# detector03.net
KiCad netlist of a schematic drawn in EAGLE
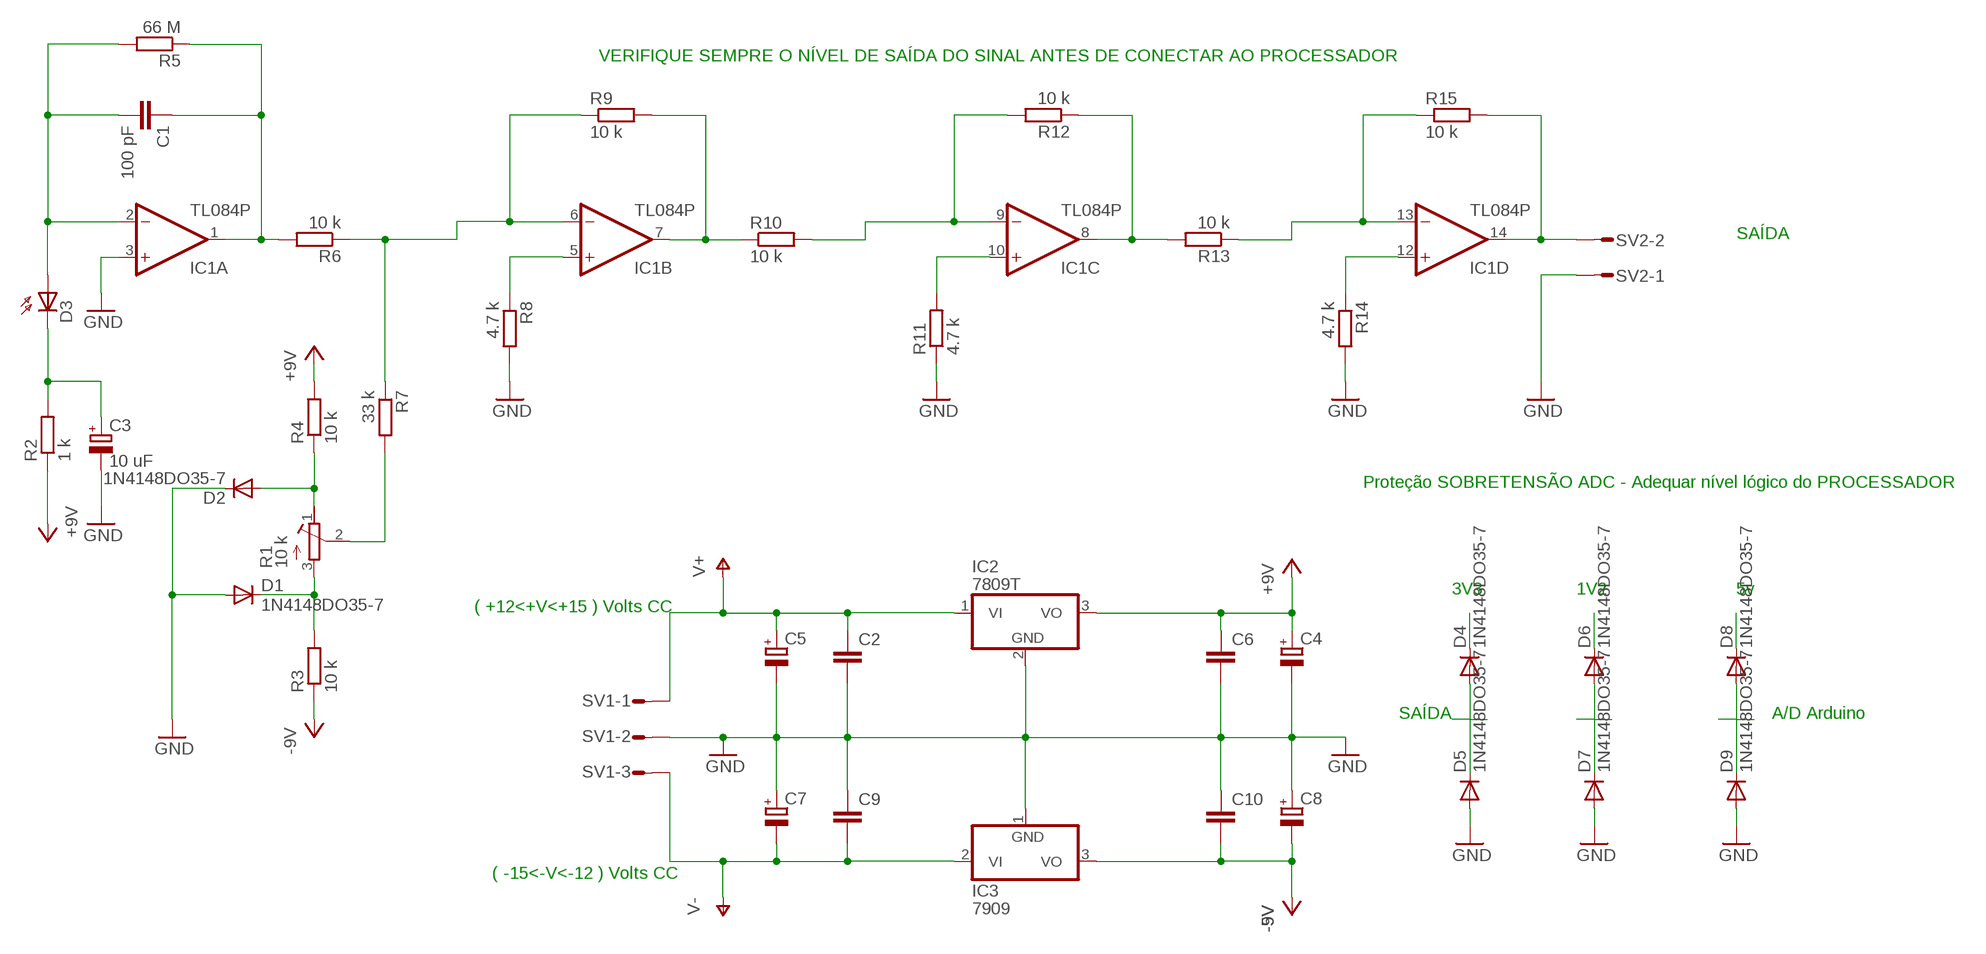
[diagram p0: schematic, sheet 1]

(export (version "E")
  (design (tool "Eeschema 10.0.6"))
  (components
    (comp (ref "C1")
      (value "100 pF")
      (footprint "eagle-import:C050-045X075")
      (libsource (lib "eagle-import") (part "C-EU050-045X075"))
    )
    (comp (ref "C2")
      (value "C-EU050-045X075")
      (footprint "eagle-import:C050-045X075")
      (libsource (lib "eagle-import") (part "C-EU050-045X075"))
    )
    (comp (ref "C3")
      (value "10 uF")
      (footprint "eagle-import:E3,5-8")
      (libsource (lib "eagle-import") (part "CPOL-EUE3.5-8"))
    )
    (comp (ref "C4")
      (value "CPOL-EUE3.5-8")
      (footprint "eagle-import:E3,5-8")
      (libsource (lib "eagle-import") (part "CPOL-EUE3.5-8"))
    )
    (comp (ref "C5")
      (value "CPOL-EUE3.5-8")
      (footprint "eagle-import:E3,5-8")
      (libsource (lib "eagle-import") (part "CPOL-EUE3.5-8"))
    )
    (comp (ref "C6")
      (value "C-EU050-045X075")
      (footprint "eagle-import:C050-045X075")
      (libsource (lib "eagle-import") (part "C-EU050-045X075"))
    )
    (comp (ref "C7")
      (value "CPOL-EUE3.5-8")
      (footprint "eagle-import:E3,5-8")
      (libsource (lib "eagle-import") (part "CPOL-EUE3.5-8"))
    )
    (comp (ref "C8")
      (value "CPOL-EUE3.5-8")
      (footprint "eagle-import:E3,5-8")
      (libsource (lib "eagle-import") (part "CPOL-EUE3.5-8"))
    )
    (comp (ref "C9")
      (value "C-EU050-045X075")
      (footprint "eagle-import:C050-045X075")
      (libsource (lib "eagle-import") (part "C-EU050-045X075"))
    )
    (comp (ref "C10")
      (value "C-EU050-045X075")
      (footprint "eagle-import:C050-045X075")
      (libsource (lib "eagle-import") (part "C-EU050-045X075"))
    )
    (comp (ref "D1")
      (value "1N4148DO35-7")
      (footprint "eagle-import:DO35-7")
      (libsource (lib "eagle-import") (part "1N4148DO35-7"))
    )
    (comp (ref "D2")
      (value "1N4148DO35-7")
      (footprint "eagle-import:DO35-7")
      (libsource (lib "eagle-import") (part "1N4148DO35-7"))
    )
    (comp (ref "D3")
      (value "SFH225")
      (footprint "eagle-import:SFH225")
      (libsource (lib "eagle-import") (part "SFH225"))
    )
    (comp (ref "D4")
      (value "1N4148DO35-7")
      (footprint "eagle-import:DO35-7")
      (libsource (lib "eagle-import") (part "1N4148DO35-7"))
    )
    (comp (ref "D5")
      (value "1N4148DO35-7")
      (footprint "eagle-import:DO35-7")
      (libsource (lib "eagle-import") (part "1N4148DO35-7"))
    )
    (comp (ref "D6")
      (value "1N4148DO35-7")
      (footprint "eagle-import:DO35-7")
      (libsource (lib "eagle-import") (part "1N4148DO35-7"))
    )
    (comp (ref "D7")
      (value "1N4148DO35-7")
      (footprint "eagle-import:DO35-7")
      (libsource (lib "eagle-import") (part "1N4148DO35-7"))
    )
    (comp (ref "D8")
      (value "1N4148DO35-7")
      (footprint "eagle-import:DO35-7")
      (libsource (lib "eagle-import") (part "1N4148DO35-7"))
    )
    (comp (ref "D9")
      (value "1N4148DO35-7")
      (footprint "eagle-import:DO35-7")
      (libsource (lib "eagle-import") (part "1N4148DO35-7"))
    )
    (comp (ref "IC1")
      (value "TL084P")
      (footprint "eagle-import:DIL14")
      (libsource (lib "eagle-import") (part "TL084P"))
    )
    (comp (ref "IC2")
      (value "7809T")
      (footprint "eagle-import:TO220H")
      (libsource (lib "eagle-import") (part "78T05"))
    )
    (comp (ref "IC3")
      (value "7909")
      (footprint "eagle-import:TO220H")
      (libsource (lib "eagle-import") (part "79T08"))
    )
    (comp (ref "R1")
      (value "10 k")
      (footprint "eagle-import:RTRIMT93YA")
      (libsource (lib "eagle-import") (part "R-TRIMMT93YA"))
    )
    (comp (ref "R2")
      (value "1 k")
      (footprint "eagle-import:0207_7")
      (libsource (lib "eagle-import") (part "R-EU_0207/7"))
    )
    (comp (ref "R3")
      (value "10 k")
      (footprint "eagle-import:0207_7")
      (libsource (lib "eagle-import") (part "R-EU_0207/7"))
    )
    (comp (ref "R4")
      (value "10 k")
      (footprint "eagle-import:0207_7")
      (libsource (lib "eagle-import") (part "R-EU_0207/7"))
    )
    (comp (ref "R5")
      (value "66 M")
      (footprint "eagle-import:0207_7")
      (libsource (lib "eagle-import") (part "R-EU_0207/7"))
    )
    (comp (ref "R6")
      (value "10 k")
      (footprint "eagle-import:0207_7")
      (libsource (lib "eagle-import") (part "R-EU_0207/7"))
    )
    (comp (ref "R7")
      (value "33 k")
      (footprint "eagle-import:0207_7")
      (libsource (lib "eagle-import") (part "R-EU_0207/7"))
    )
    (comp (ref "R8")
      (value "4.7 k")
      (footprint "eagle-import:0207_7")
      (libsource (lib "eagle-import") (part "R-EU_0207/7"))
    )
    (comp (ref "R9")
      (value "10 k")
      (footprint "eagle-import:0207_7")
      (libsource (lib "eagle-import") (part "R-EU_0207/7"))
    )
    (comp (ref "R10")
      (value "10 k")
      (footprint "eagle-import:0207_7")
      (libsource (lib "eagle-import") (part "R-EU_0207/7"))
    )
    (comp (ref "R11")
      (value "4.7 k")
      (footprint "eagle-import:0207_7")
      (libsource (lib "eagle-import") (part "R-EU_0207/7"))
    )
    (comp (ref "R12")
      (value "10 k")
      (footprint "eagle-import:0207_7")
      (libsource (lib "eagle-import") (part "R-EU_0207/7"))
    )
    (comp (ref "R13")
      (value "10 k")
      (footprint "eagle-import:0207_7")
      (libsource (lib "eagle-import") (part "R-EU_0207/7"))
    )
    (comp (ref "R14")
      (value "4.7 k")
      (footprint "eagle-import:0207_7")
      (libsource (lib "eagle-import") (part "R-EU_0207/7"))
    )
    (comp (ref "R15")
      (value "10 k")
      (footprint "eagle-import:0207_7")
      (libsource (lib "eagle-import") (part "R-EU_0207/7"))
    )
    (comp (ref "SV1")
      (value "L03P")
      (footprint "eagle-import:L03P")
      (libsource (lib "eagle-import") (part "L03P"))
    )
    (comp (ref "SV2")
      (value "L02P")
      (footprint "eagle-import:L02P")
      (libsource (lib "eagle-import") (part "L02P"))
    )
  )
  (nets
    (net (code "1") (name "+9V") (class "Default")
      (node (ref "C4") (pin "+") (pinfunction "+_+") (pintype "passive"))
      (node (ref "C6") (pin "1") (pinfunction "1_1") (pintype "passive"))
      (node (ref "IC2") (pin "3") (pinfunction "VO_3") (pintype "passive"))
      (node (ref "R2") (pin "1") (pinfunction "1_1") (pintype "passive"))
      (node (ref "R4") (pin "2") (pinfunction "2_2") (pintype "passive"))
    )
    (net (code "2") (name "-5V") (class "Default")
      (node (ref "C10") (pin "2") (pinfunction "2_2") (pintype "passive"))
      (node (ref "C8") (pin "-") (pinfunction "-_-") (pintype "passive"))
      (node (ref "IC3") (pin "3") (pinfunction "VO_3") (pintype "passive"))
      (node (ref "R3") (pin "1") (pinfunction "1_1") (pintype "passive"))
    )
    (net (code "3") (name "GND") (class "Default")
      (node (ref "C10") (pin "1") (pinfunction "1_1") (pintype "passive"))
      (node (ref "C2") (pin "2") (pinfunction "2_2") (pintype "passive"))
      (node (ref "C3") (pin "-") (pinfunction "-_-") (pintype "passive"))
      (node (ref "C4") (pin "-") (pinfunction "-_-") (pintype "passive"))
      (node (ref "C5") (pin "-") (pinfunction "-_-") (pintype "passive"))
      (node (ref "C6") (pin "2") (pinfunction "2_2") (pintype "passive"))
      (node (ref "C7") (pin "+") (pinfunction "+_+") (pintype "passive"))
      (node (ref "C8") (pin "+") (pinfunction "+_+") (pintype "passive"))
      (node (ref "C9") (pin "1") (pinfunction "1_1") (pintype "passive"))
      (node (ref "D1") (pin "A") (pinfunction "A_A") (pintype "passive"))
      (node (ref "D2") (pin "C") (pinfunction "C_C") (pintype "passive"))
      (node (ref "D5") (pin "A") (pinfunction "A_A") (pintype "passive"))
      (node (ref "D7") (pin "A") (pinfunction "A_A") (pintype "passive"))
      (node (ref "D9") (pin "A") (pinfunction "A_A") (pintype "passive"))
      (node (ref "IC1") (pin "3") (pinfunction "+IN_3") (pintype "input"))
      (node (ref "IC2") (pin "2") (pinfunction "GND_2") (pintype "passive"))
      (node (ref "IC3") (pin "1") (pinfunction "GND_1") (pintype "passive"))
      (node (ref "R11") (pin "1") (pinfunction "1_1") (pintype "passive"))
      (node (ref "R14") (pin "2") (pinfunction "2_2") (pintype "passive"))
      (node (ref "R8") (pin "2") (pinfunction "2_2") (pintype "passive"))
      (node (ref "SV1") (pin "2") (pinfunction "S_2") (pintype "passive"))
      (node (ref "SV2") (pin "1") (pinfunction "S_1") (pintype "passive"))
    )
    (net (code "4") (name "Net-(D3-C)") (class "Default")
      (node (ref "C3") (pin "+") (pinfunction "+_+") (pintype "passive"))
      (node (ref "D3") (pin "K") (pinfunction "C_K") (pintype "passive"))
      (node (ref "R2") (pin "2") (pinfunction "2_2") (pintype "passive"))
    )
    (net (code "5") (name "Net-(D4-PadA)") (class "Default")
      (node (ref "D4") (pin "A") (pinfunction "A_A") (pintype "passive"))
      (node (ref "D5") (pin "C") (pinfunction "C_C") (pintype "passive"))
    )
    (net (code "6") (name "Net-(D6-PadA)") (class "Default")
      (node (ref "D6") (pin "A") (pinfunction "A_A") (pintype "passive"))
      (node (ref "D7") (pin "C") (pinfunction "C_C") (pintype "passive"))
    )
    (net (code "7") (name "Net-(D8-PadA)") (class "Default")
      (node (ref "D8") (pin "A") (pinfunction "A_A") (pintype "passive"))
      (node (ref "D9") (pin "C") (pinfunction "C_C") (pintype "passive"))
    )
    (net (code "8") (name "Net-(IC1A--IN)") (class "Default")
      (node (ref "C1") (pin "2") (pinfunction "2_2") (pintype "passive"))
      (node (ref "D3") (pin "A") (pinfunction "A_A") (pintype "passive"))
      (node (ref "IC1") (pin "2") (pinfunction "-IN_2") (pintype "input"))
      (node (ref "R5") (pin "2") (pinfunction "2_2") (pintype "passive"))
    )
    (net (code "9") (name "Net-(IC1A-OUT)") (class "Default")
      (node (ref "C1") (pin "1") (pinfunction "1_1") (pintype "passive"))
      (node (ref "IC1") (pin "1") (pinfunction "OUT_1") (pintype "output"))
      (node (ref "R5") (pin "1") (pinfunction "1_1") (pintype "passive"))
      (node (ref "R6") (pin "2") (pinfunction "2_2") (pintype "passive"))
    )
    (net (code "10") (name "Net-(IC1B-+IN)") (class "Default")
      (node (ref "IC1") (pin "5") (pinfunction "+IN_5") (pintype "input"))
      (node (ref "R8") (pin "1") (pinfunction "1_1") (pintype "passive"))
    )
    (net (code "11") (name "Net-(IC1B--IN)") (class "Default")
      (node (ref "IC1") (pin "6") (pinfunction "-IN_6") (pintype "input"))
      (node (ref "R6") (pin "1") (pinfunction "1_1") (pintype "passive"))
      (node (ref "R7") (pin "1") (pinfunction "1_1") (pintype "passive"))
      (node (ref "R9") (pin "1") (pinfunction "1_1") (pintype "passive"))
    )
    (net (code "12") (name "Net-(IC1B-OUT)") (class "Default")
      (node (ref "IC1") (pin "7") (pinfunction "OUT_7") (pintype "output"))
      (node (ref "R10") (pin "1") (pinfunction "1_1") (pintype "passive"))
      (node (ref "R9") (pin "2") (pinfunction "2_2") (pintype "passive"))
    )
    (net (code "13") (name "Net-(IC1C-+IN)") (class "Default")
      (node (ref "IC1") (pin "10") (pinfunction "+IN_10") (pintype "input"))
      (node (ref "R11") (pin "2") (pinfunction "2_2") (pintype "passive"))
    )
    (net (code "14") (name "Net-(IC1C--IN)") (class "Default")
      (node (ref "IC1") (pin "9") (pinfunction "-IN_9") (pintype "input"))
      (node (ref "R10") (pin "2") (pinfunction "2_2") (pintype "passive"))
      (node (ref "R12") (pin "2") (pinfunction "2_2") (pintype "passive"))
    )
    (net (code "15") (name "Net-(IC1C-OUT)") (class "Default")
      (node (ref "IC1") (pin "8") (pinfunction "OUT_8") (pintype "output"))
      (node (ref "R12") (pin "1") (pinfunction "1_1") (pintype "passive"))
      (node (ref "R13") (pin "2") (pinfunction "2_2") (pintype "passive"))
    )
    (net (code "16") (name "Net-(IC1D-+IN)") (class "Default")
      (node (ref "IC1") (pin "12") (pinfunction "+IN_12") (pintype "input"))
      (node (ref "R14") (pin "1") (pinfunction "1_1") (pintype "passive"))
    )
    (net (code "17") (name "Net-(IC1D--IN)") (class "Default")
      (node (ref "IC1") (pin "13") (pinfunction "-IN_13") (pintype "input"))
      (node (ref "R13") (pin "1") (pinfunction "1_1") (pintype "passive"))
      (node (ref "R15") (pin "1") (pinfunction "1_1") (pintype "passive"))
    )
    (net (code "18") (name "Net-(IC1D-OUT)") (class "Default")
      (node (ref "IC1") (pin "14") (pinfunction "OUT_14") (pintype "output"))
      (node (ref "R15") (pin "2") (pinfunction "2_2") (pintype "passive"))
      (node (ref "SV2") (pin "2") (pinfunction "S_2") (pintype "passive"))
    )
    (net (code "19") (name "Net-(R1-A)") (class "Default")
      (node (ref "D1") (pin "C") (pinfunction "C_C") (pintype "passive"))
      (node (ref "R1") (pin "3") (pinfunction "A_3") (pintype "passive"))
      (node (ref "R3") (pin "2") (pinfunction "2_2") (pintype "passive"))
    )
    (net (code "20") (name "Net-(R1-E)") (class "Default")
      (node (ref "D2") (pin "A") (pinfunction "A_A") (pintype "passive"))
      (node (ref "R1") (pin "1") (pinfunction "E_1") (pintype "passive"))
      (node (ref "R4") (pin "1") (pinfunction "1_1") (pintype "passive"))
    )
    (net (code "21") (name "Net-(R1-S)") (class "Default")
      (node (ref "R1") (pin "2") (pinfunction "S_2") (pintype "passive"))
      (node (ref "R7") (pin "2") (pinfunction "2_2") (pintype "passive"))
    )
    (net (code "22") (name "V+") (class "Default")
      (node (ref "C2") (pin "1") (pinfunction "1_1") (pintype "passive"))
      (node (ref "C5") (pin "+") (pinfunction "+_+") (pintype "passive"))
      (node (ref "IC2") (pin "1") (pinfunction "VI_1") (pintype "input"))
      (node (ref "SV1") (pin "1") (pinfunction "S_1") (pintype "passive"))
    )
    (net (code "23") (name "V-") (class "Default")
      (node (ref "C7") (pin "-") (pinfunction "-_-") (pintype "passive"))
      (node (ref "C9") (pin "2") (pinfunction "2_2") (pintype "passive"))
      (node (ref "IC3") (pin "2") (pinfunction "VI_2") (pintype "input"))
      (node (ref "SV1") (pin "3") (pinfunction "S_3") (pintype "passive"))
    )
    (net (code "24") (name "unconnected-(D4-PadC)") (class "Default")
      (node (ref "D4") (pin "C") (pinfunction "C_C") (pintype "passive"))
    )
    (net (code "25") (name "unconnected-(D6-PadC)") (class "Default")
      (node (ref "D6") (pin "C") (pinfunction "C_C") (pintype "passive"))
    )
    (net (code "26") (name "unconnected-(D8-PadC)") (class "Default")
      (node (ref "D8") (pin "C") (pinfunction "C_C") (pintype "passive"))
    )
  )
)
